# main_4_1.net
KiCad netlist of a schematic drawn in EAGLE
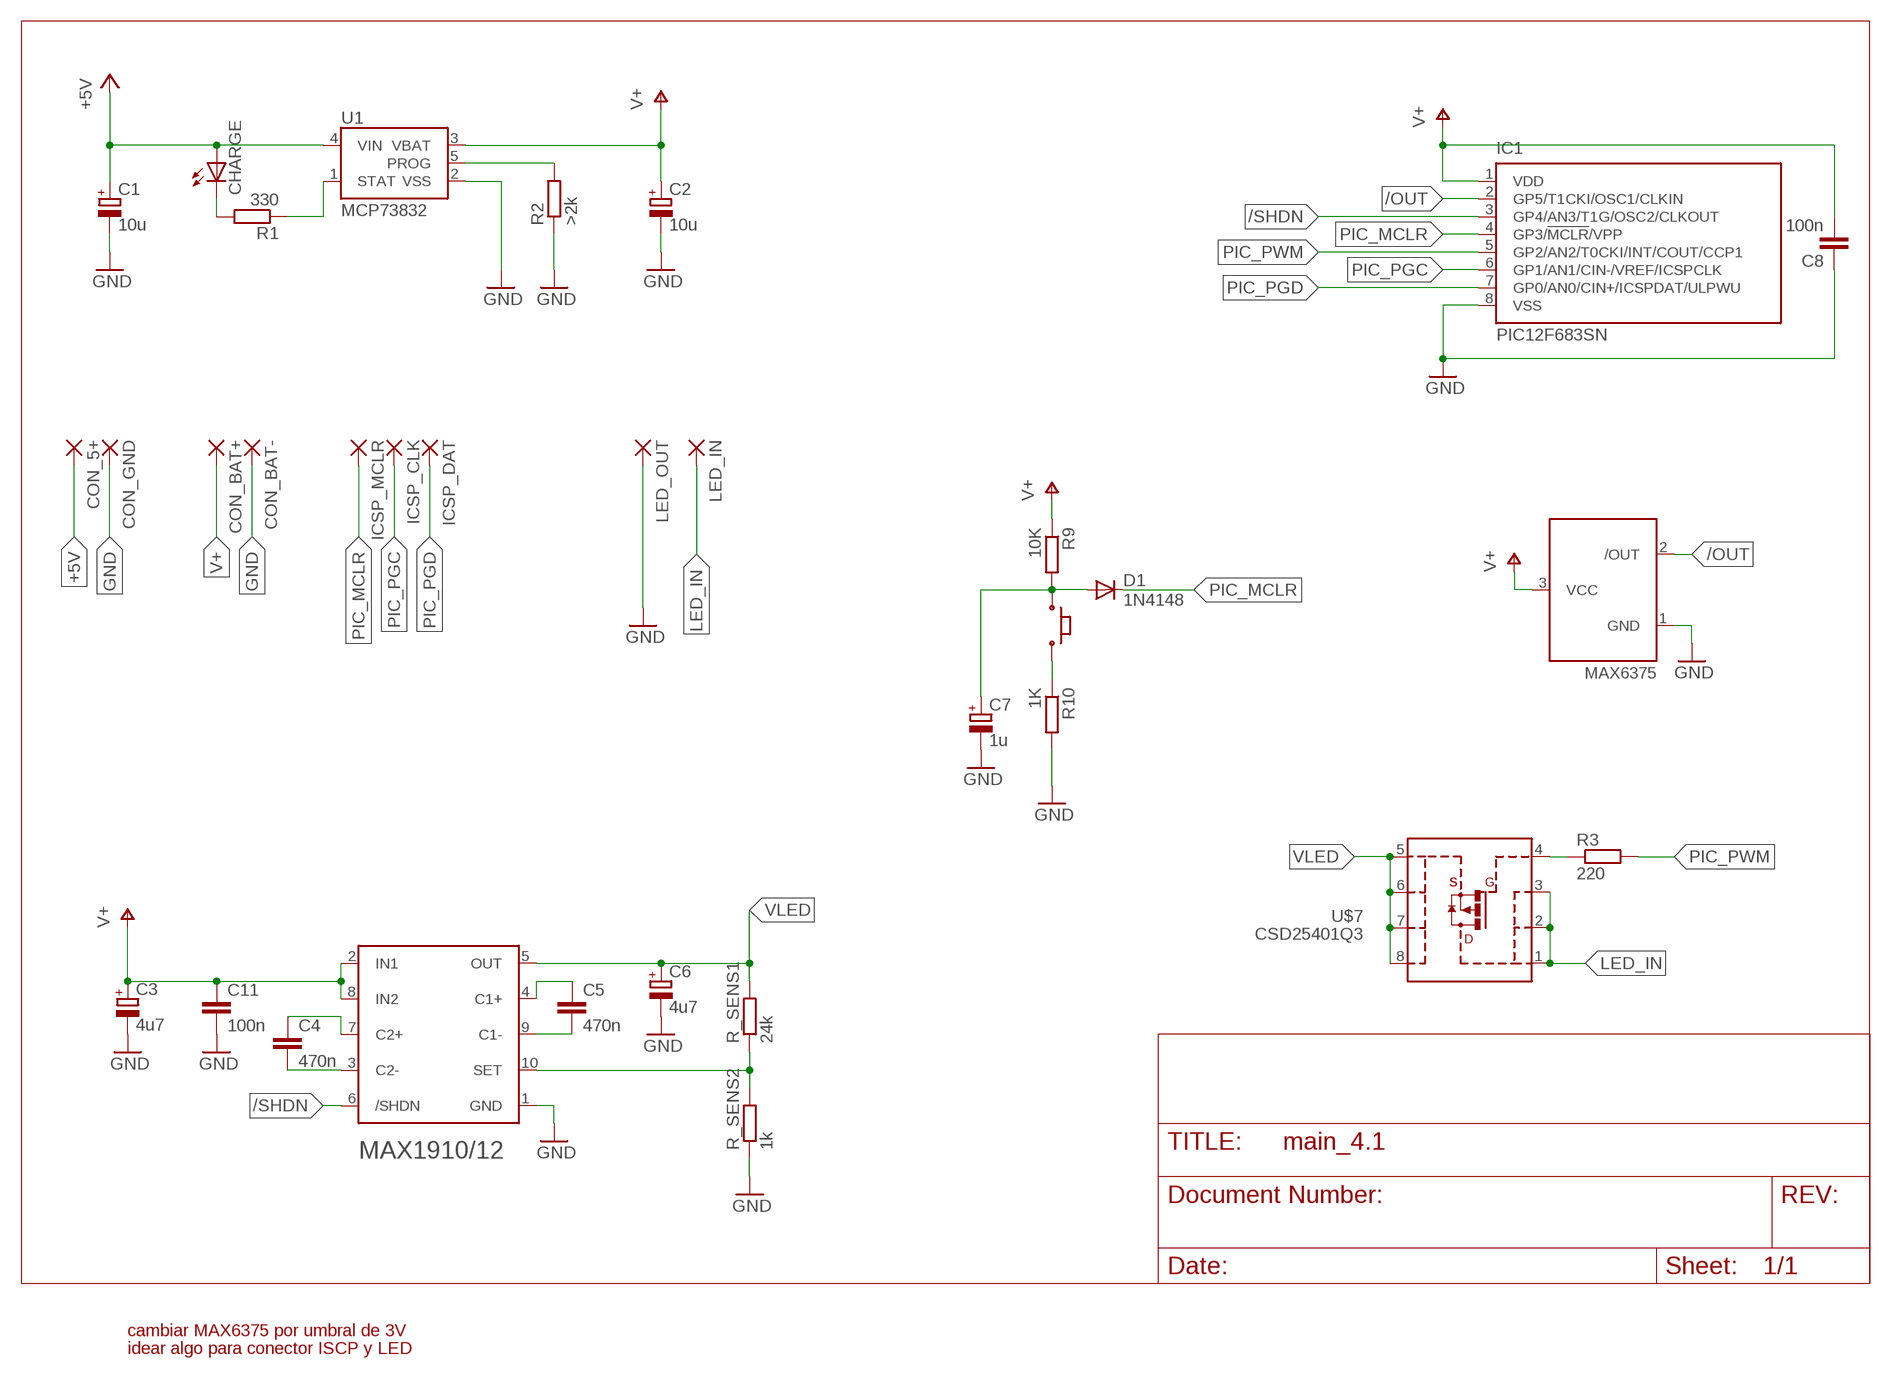
[diagram p0: schematic, sheet 1]

(export (version "E")
  (design (tool "Eeschema 10.0.6"))
  (components
    (comp (ref "C1")
      (value "10u")
      (footprint "eagle-import:SMC_A")
      (libsource (lib "eagle-import") (part "CPOL-EUSMCA"))
    )
    (comp (ref "C2")
      (value "10u")
      (footprint "eagle-import:SMC_A")
      (libsource (lib "eagle-import") (part "CPOL-EUSMCA"))
    )
    (comp (ref "C3")
      (value "4u7")
      (footprint "eagle-import:SMC_A")
      (libsource (lib "eagle-import") (part "CPOL-EUSMCA"))
    )
    (comp (ref "C4")
      (value "470n")
      (footprint "eagle-import:C1206")
      (libsource (lib "eagle-import") (part "C-EUC1206"))
    )
    (comp (ref "C5")
      (value "470n")
      (footprint "eagle-import:C1206")
      (libsource (lib "eagle-import") (part "C-EUC1206"))
    )
    (comp (ref "C6")
      (value "4u7")
      (footprint "eagle-import:SMC_A")
      (libsource (lib "eagle-import") (part "CPOL-EUSMCA"))
    )
    (comp (ref "C7")
      (value "1u")
      (footprint "eagle-import:SMC_A")
      (libsource (lib "eagle-import") (part "CPOL-EUSMCA"))
    )
    (comp (ref "C8")
      (value "100n")
      (footprint "eagle-import:C1206")
      (libsource (lib "eagle-import") (part "C-EUC1206"))
    )
    (comp (ref "C11")
      (value "100n")
      (footprint "eagle-import:C1206")
      (libsource (lib "eagle-import") (part "C-EUC1206"))
    )
    (comp (ref "CHARGE")
      (value "LEDCHIPLED_1206")
      (footprint "eagle-import:CHIPLED_1206")
      (libsource (lib "eagle-import") (part "LEDCHIPLED_1206"))
    )
    (comp (ref "CON_5+")
      (value "SMD5")
      (footprint "eagle-import:SMD2,54-5,08")
      (libsource (lib "eagle-import") (part "SMD5"))
    )
    (comp (ref "CON_BAT+")
      (value "SMD5")
      (footprint "eagle-import:SMD2,54-5,08")
      (libsource (lib "eagle-import") (part "SMD5"))
    )
    (comp (ref "CON_BAT-")
      (value "SMD5")
      (footprint "eagle-import:SMD2,54-5,08")
      (libsource (lib "eagle-import") (part "SMD5"))
    )
    (comp (ref "CON_GND")
      (value "SMD5")
      (footprint "eagle-import:SMD2,54-5,08")
      (libsource (lib "eagle-import") (part "SMD5"))
    )
    (comp (ref "D1")
      (value "1N4148")
      (footprint "eagle-import:SOD80")
      (libsource (lib "eagle-import") (part "1N4148"))
    )
    (comp (ref "IC1")
      (value "PIC12F683SN")
      (footprint "eagle-import:SO-08")
      (fields (field (name "MF") "MICROCHIP") (field (name "MPN") "PIC12F683-I/SN"))
      (libsource (lib "eagle-import") (part "PIC12F683SN"))
    )
    (comp (ref "ICSP_CLK")
      (value "SMD5")
      (footprint "eagle-import:SMD2,54-5,08")
      (libsource (lib "eagle-import") (part "SMD5"))
    )
    (comp (ref "ICSP_DAT")
      (value "SMD5")
      (footprint "eagle-import:SMD2,54-5,08")
      (libsource (lib "eagle-import") (part "SMD5"))
    )
    (comp (ref "ICSP_MCLR")
      (value "SMD5")
      (footprint "eagle-import:SMD2,54-5,08")
      (libsource (lib "eagle-import") (part "SMD5"))
    )
    (comp (ref "LED_IN")
      (value "SMD5")
      (footprint "eagle-import:SMD2,54-5,08")
      (libsource (lib "eagle-import") (part "SMD5"))
    )
    (comp (ref "LED_OUT")
      (value "SMD5")
      (footprint "eagle-import:SMD2,54-5,08")
      (libsource (lib "eagle-import") (part "SMD5"))
    )
    (comp (ref "R1")
      (value "330")
      (footprint "eagle-import:R1206")
      (libsource (lib "eagle-import") (part "R-EU_R1206"))
    )
    (comp (ref "R2")
      (value ">2k")
      (footprint "eagle-import:R1206")
      (libsource (lib "eagle-import") (part "R-EU_R1206"))
    )
    (comp (ref "R3")
      (value "220")
      (footprint "eagle-import:R1206")
      (libsource (lib "eagle-import") (part "R-EU_R1206"))
    )
    (comp (ref "R9")
      (value "10K")
      (footprint "eagle-import:R1206")
      (libsource (lib "eagle-import") (part "R-EU_R1206"))
    )
    (comp (ref "R10")
      (value "1K")
      (footprint "eagle-import:R1206")
      (libsource (lib "eagle-import") (part "R-EU_R1206"))
    )
    (comp (ref "R_SENS1")
      (value "24k")
      (footprint "eagle-import:R1206")
      (libsource (lib "eagle-import") (part "R-EU_R1206"))
    )
    (comp (ref "R_SENS2")
      (value "1k")
      (footprint "eagle-import:R1206")
      (libsource (lib "eagle-import") (part "R-EU_R1206"))
    )
    (comp (ref "U$1")
      (value "MAX1910/12")
      (footprint "eagle-import:UMAX_USOP_10L")
      (libsource (lib "eagle-import") (part "MAX1910/12"))
    )
    (comp (ref "U$2")
      (value "MAX6375")
      (footprint "eagle-import:SC70-3-W")
      (libsource (lib "eagle-import") (part "MAX6375"))
    )
    (comp (ref "U$6")
      (value "MICROBUTTONE-MERCHAN")
      (footprint "eagle-import:MICROBUTTON_2")
      (libsource (lib "eagle-import") (part "MICROBUTTONE-MERCHAN"))
    )
    (comp (ref "U$7")
      (value "CSD25401Q3")
      (footprint "eagle-import:SON3X3")
      (libsource (lib "eagle-import") (part "CSD25401Q3"))
    )
    (comp (ref "U1")
      (value "MCP73832")
      (footprint "eagle-import:SOT23-5")
      (libsource (lib "eagle-import") (part "MCP73832"))
    )
  )
  (nets
    (net (code "1") (name "+5V") (class "Default")
      (node (ref "C1") (pin "+") (pinfunction "+_+") (pintype "passive"))
      (node (ref "CHARGE") (pin "A") (pinfunction "A_A") (pintype "passive"))
      (node (ref "CON_5+") (pin "1") (pinfunction "P_1") (pintype "passive"))
      (node (ref "U1") (pin "4") (pinfunction "VIN_4") (pintype "power_in"))
    )
    (net (code "2") (name "GND") (class "Default")
      (node (ref "C1") (pin "-") (pinfunction "-_-") (pintype "passive"))
      (node (ref "C11") (pin "2") (pinfunction "2_2") (pintype "passive"))
      (node (ref "C2") (pin "-") (pinfunction "-_-") (pintype "passive"))
      (node (ref "C3") (pin "-") (pinfunction "-_-") (pintype "passive"))
      (node (ref "C6") (pin "-") (pinfunction "-_-") (pintype "passive"))
      (node (ref "C7") (pin "-") (pinfunction "-_-") (pintype "passive"))
      (node (ref "C8") (pin "1") (pinfunction "1_1") (pintype "passive"))
      (node (ref "CON_BAT-") (pin "1") (pinfunction "P_1") (pintype "passive"))
      (node (ref "CON_GND") (pin "1") (pinfunction "P_1") (pintype "passive"))
      (node (ref "IC1") (pin "8") (pinfunction "VSS_8") (pintype "power_in"))
      (node (ref "LED_OUT") (pin "1") (pinfunction "P_1") (pintype "passive"))
      (node (ref "R10") (pin "2") (pinfunction "2_2") (pintype "passive"))
      (node (ref "R2") (pin "1") (pinfunction "1_1") (pintype "passive"))
      (node (ref "R_SENS2") (pin "1") (pinfunction "1_1") (pintype "passive"))
      (node (ref "U$1") (pin "1") (pinfunction "GND_1") (pintype "power_in"))
      (node (ref "U$2") (pin "1") (pinfunction "GND_1") (pintype "power_in"))
      (node (ref "U1") (pin "2") (pinfunction "VSS_2") (pintype "power_in"))
    )
    (net (code "3") (name "LED_IN") (class "Default")
      (node (ref "LED_IN") (pin "1") (pinfunction "P_1") (pintype "passive"))
      (node (ref "U$7") (pin "1") (pinfunction "D$1_1") (pintype "bidirectional"))
      (node (ref "U$7") (pin "2") (pinfunction "D$2_2") (pintype "bidirectional"))
      (node (ref "U$7") (pin "3") (pinfunction "D$3_3") (pintype "bidirectional"))
    )
    (net (code "4") (name "Net-(CHARGE-PadC)") (class "Default")
      (node (ref "CHARGE") (pin "C") (pinfunction "C_C") (pintype "passive"))
      (node (ref "R1") (pin "2") (pinfunction "2_2") (pintype "passive"))
    )
    (net (code "5") (name "Net-(D1-A)") (class "Default")
      (node (ref "C7") (pin "+") (pinfunction "+_+") (pintype "passive"))
      (node (ref "D1") (pin "1") (pinfunction "A_1") (pintype "passive"))
      (node (ref "R9") (pin "2") (pinfunction "2_2") (pintype "passive"))
      (node (ref "U$6") (pin "P$1") (pinfunction "P$1_P$1") (pintype "bidirectional"))
    )
    (net (code "6") (name "Net-(R10-Pad1)") (class "Default")
      (node (ref "R10") (pin "1") (pinfunction "1_1") (pintype "passive"))
      (node (ref "U$6") (pin "P$2") (pinfunction "P$2_P$2") (pintype "bidirectional"))
    )
    (net (code "7") (name "Net-(U$1-C1+)") (class "Default")
      (node (ref "C5") (pin "1") (pinfunction "1_1") (pintype "passive"))
      (node (ref "U$1") (pin "4") (pinfunction "C1+_4") (pintype "bidirectional"))
    )
    (net (code "8") (name "Net-(U$1-C1-)") (class "Default")
      (node (ref "C5") (pin "2") (pinfunction "2_2") (pintype "passive"))
      (node (ref "U$1") (pin "9") (pinfunction "C1-_9") (pintype "bidirectional"))
    )
    (net (code "9") (name "Net-(U$1-C2+)") (class "Default")
      (node (ref "C4") (pin "1") (pinfunction "1_1") (pintype "passive"))
      (node (ref "U$1") (pin "7") (pinfunction "C2+_7") (pintype "bidirectional"))
    )
    (net (code "10") (name "Net-(U$1-C2-)") (class "Default")
      (node (ref "C4") (pin "2") (pinfunction "2_2") (pintype "passive"))
      (node (ref "U$1") (pin "3") (pinfunction "C2-_3") (pintype "bidirectional"))
    )
    (net (code "11") (name "Net-(U$1-SET)") (class "Default")
      (node (ref "R_SENS1") (pin "1") (pinfunction "1_1") (pintype "passive"))
      (node (ref "R_SENS2") (pin "2") (pinfunction "2_2") (pintype "passive"))
      (node (ref "U$1") (pin "10") (pinfunction "SET_10") (pintype "input"))
    )
    (net (code "12") (name "Net-(U$7-G$4)") (class "Default")
      (node (ref "R3") (pin "1") (pinfunction "1_1") (pintype "passive"))
      (node (ref "U$7") (pin "4") (pinfunction "G$4_4") (pintype "bidirectional"))
    )
    (net (code "13") (name "Net-(U1-PROG)") (class "Default")
      (node (ref "R2") (pin "2") (pinfunction "2_2") (pintype "passive"))
      (node (ref "U1") (pin "5") (pinfunction "PROG_5") (pintype "input"))
    )
    (net (code "14") (name "Net-(U1-STAT)") (class "Default")
      (node (ref "R1") (pin "1") (pinfunction "1_1") (pintype "passive"))
      (node (ref "U1") (pin "1") (pinfunction "STAT_1") (pintype "output"))
    )
    (net (code "15") (name "PIC_MCLR") (class "Default")
      (node (ref "D1") (pin "2") (pinfunction "C_2") (pintype "passive"))
      (node (ref "IC1") (pin "4") (pinfunction "GP3/~{MCLR}/VPP_4") (pintype "bidirectional"))
      (node (ref "ICSP_MCLR") (pin "1") (pinfunction "P_1") (pintype "passive"))
    )
    (net (code "16") (name "PIC_PGC") (class "Default")
      (node (ref "IC1") (pin "6") (pinfunction "GP1/AN1/CIN-/VREF/ICSPCLK_6") (pintype "bidirectional"))
      (node (ref "ICSP_CLK") (pin "1") (pinfunction "P_1") (pintype "passive"))
    )
    (net (code "17") (name "PIC_PGD") (class "Default")
      (node (ref "IC1") (pin "7") (pinfunction "GP0/AN0/CIN+/ICSPDAT/ULPWU_7") (pintype "bidirectional"))
      (node (ref "ICSP_DAT") (pin "1") (pinfunction "P_1") (pintype "passive"))
    )
    (net (code "18") (name "PIC_PWM") (class "Default")
      (node (ref "IC1") (pin "5") (pinfunction "GP2/AN2/T0CKI/INT/COUT/CCP1_5") (pintype "bidirectional"))
      (node (ref "R3") (pin "2") (pinfunction "2_2") (pintype "passive"))
    )
    (net (code "19") (name "V+") (class "Default")
      (node (ref "C11") (pin "1") (pinfunction "1_1") (pintype "passive"))
      (node (ref "C2") (pin "+") (pinfunction "+_+") (pintype "passive"))
      (node (ref "C3") (pin "+") (pinfunction "+_+") (pintype "passive"))
      (node (ref "C8") (pin "2") (pinfunction "2_2") (pintype "passive"))
      (node (ref "CON_BAT+") (pin "1") (pinfunction "P_1") (pintype "passive"))
      (node (ref "IC1") (pin "1") (pinfunction "VDD_1") (pintype "power_in"))
      (node (ref "R9") (pin "1") (pinfunction "1_1") (pintype "passive"))
      (node (ref "U$1") (pin "2") (pinfunction "IN1_2") (pintype "power_in"))
      (node (ref "U$1") (pin "8") (pinfunction "IN2_8") (pintype "power_in"))
      (node (ref "U$2") (pin "3") (pinfunction "VCC_3") (pintype "power_in"))
      (node (ref "U1") (pin "3") (pinfunction "VBAT_3") (pintype "power_in"))
    )
    (net (code "20") (name "VLED") (class "Default")
      (node (ref "C6") (pin "+") (pinfunction "+_+") (pintype "passive"))
      (node (ref "R_SENS1") (pin "2") (pinfunction "2_2") (pintype "passive"))
      (node (ref "U$1") (pin "5") (pinfunction "OUT_5") (pintype "output"))
      (node (ref "U$7") (pin "5") (pinfunction "S$5_5") (pintype "bidirectional"))
      (node (ref "U$7") (pin "6") (pinfunction "S$6_6") (pintype "bidirectional"))
      (node (ref "U$7") (pin "7") (pinfunction "S$7_7") (pintype "bidirectional"))
      (node (ref "U$7") (pin "8") (pinfunction "S$8_8") (pintype "bidirectional"))
    )
    (net (code "21") (name "{slash}OUT") (class "Default")
      (node (ref "IC1") (pin "2") (pinfunction "GP5/T1CKI/OSC1/CLKIN_2") (pintype "bidirectional"))
      (node (ref "U$2") (pin "2") (pinfunction "/OUT_2") (pintype "output"))
    )
    (net (code "22") (name "{slash}SHDN") (class "Default")
      (node (ref "IC1") (pin "3") (pinfunction "GP4/AN3/T1G/OSC2/CLKOUT_3") (pintype "bidirectional"))
      (node (ref "U$1") (pin "6") (pinfunction "/SHDN_6") (pintype "bidirectional"))
    )
  )
)
